# Sheet1.net
KiCad netlist of a schematic drawn in Altium Designer
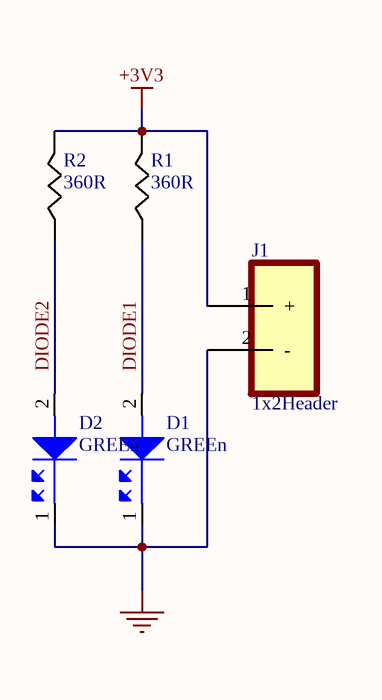
[diagram p0: Sheet1.SchDoc]

(export (version "E")
  (design (tool "Eeschema 10.0.6"))
  (components
    (comp (ref "D1")
      (value "GREEn")
      (footprint "LEd0603G")
      (description "LED GREEN CLEAR CHIP 0603 SMD")
      (fields
        (field (name "MANUFACTURER") "Visual Communications")
        (field (name "MANUFACTURER PART NUMBER") "LSM0603453V")
      )
      (libsource (lib "LedschLib") (part "LSM0603453V"))
    )
    (comp (ref "D2")
      (value "GREEn")
      (footprint "LEd0603G")
      (description "LED GREEN CLEAR CHIP 0603 SMD")
      (fields
        (field (name "MANUFACTURER") "Visual Communications")
        (field (name "MANUFACTURER PART NUMBER") "LSM0603453V")
      )
      (libsource (lib "LedschLib") (part "LSM0603453V"))
    )
    (comp (ref "J1")
      (value "1x2Header")
      (footprint "HDR1x2")
      (description "CONN HEADER VERT 2POS 2.54MMT")
      (fields (field (name "MANUFACTURER") "Molex") (field (name "MANUFACTURER PART NUMBER") "22-27-2021"))
      (libsource (lib "LedschLib") (part "22-27-2021 (3)"))
    )
    (comp (ref "R1")
      (value "360R")
      (footprint "R0805")
      (description "RES SMD 360 OHM 1% 1/8W 0805")
      (fields
        (field (name "MANUFACTURER") "Yageo")
        (field (name "MANUFACTURER PART NUMBER") "AC0805FR-07360RL")
      )
      (libsource (lib "LedschLib") (part "AC0805FR-07360RL"))
    )
    (comp (ref "R2")
      (value "360R")
      (footprint "R0805")
      (description "RES SMD 360 OHM 1% 1/8W 0805")
      (fields
        (field (name "MANUFACTURER") "Yageo")
        (field (name "MANUFACTURER PART NUMBER") "AC0805FR-07360RL")
      )
      (libsource (lib "LedschLib") (part "AC0805FR-07360RL"))
    )
  )
  (nets
    (net (code "1") (name "+3V3") (class "Default")
      (node (ref "J1") (pin "1") (pinfunction "+_1") (pintype "passive"))
      (node (ref "R1") (pin "2") (pinfunction "2_2") (pintype "passive"))
      (node (ref "R2") (pin "2") (pinfunction "2_2") (pintype "passive"))
    )
    (net (code "2") (name "/DIODE1") (class "Default")
      (node (ref "D1") (pin "2") (pinfunction "2_2") (pintype "passive"))
      (node (ref "R1") (pin "1") (pinfunction "1_1") (pintype "passive"))
    )
    (net (code "3") (name "/DIODE2") (class "Default")
      (node (ref "D2") (pin "2") (pinfunction "2_2") (pintype "passive"))
      (node (ref "R2") (pin "1") (pinfunction "1_1") (pintype "passive"))
    )
    (net (code "4") (name "GND") (class "Default")
      (node (ref "D1") (pin "1") (pinfunction "1_1") (pintype "passive"))
      (node (ref "D2") (pin "1") (pinfunction "1_1") (pintype "passive"))
      (node (ref "J1") (pin "2") (pinfunction "-_2") (pintype "passive"))
    )
  )
)
